# DIY_tool_-_Arduino_nano_shield_v1.net
KiCad netlist of a schematic drawn in EAGLE
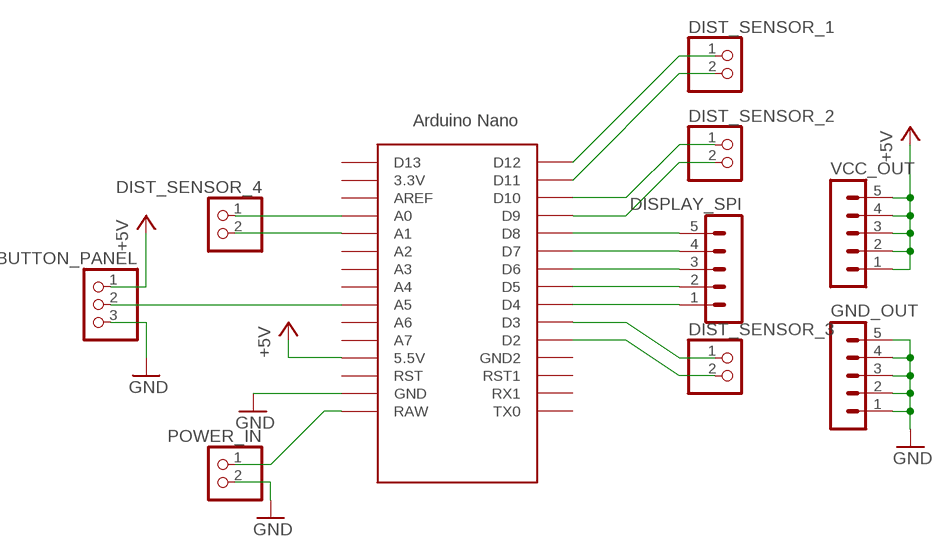
[diagram p0: schematic, sheet 1]

(export (version "E")
  (design (tool "Eeschema 10.0.6"))
  (components
    (comp (ref "BUTTON_PANEL")
      (value "PINHD-1X3")
      (footprint "eagle-import:1X03")
      (libsource (lib "eagle-import") (part "PINHD-1X3"))
    )
    (comp (ref "DISPLAY_SPI")
      (value "MA05-1")
      (footprint "eagle-import:MA05-1")
      (libsource (lib "eagle-import") (part "MA05-1"))
    )
    (comp (ref "DIST_SENSOR_1")
      (value "PINHD-1X2")
      (footprint "eagle-import:1X02")
      (libsource (lib "eagle-import") (part "PINHD-1X2"))
    )
    (comp (ref "DIST_SENSOR_2")
      (value "PINHD-1X2")
      (footprint "eagle-import:1X02")
      (libsource (lib "eagle-import") (part "PINHD-1X2"))
    )
    (comp (ref "DIST_SENSOR_3")
      (value "PINHD-1X2")
      (footprint "eagle-import:1X02")
      (libsource (lib "eagle-import") (part "PINHD-1X2"))
    )
    (comp (ref "DIST_SENSOR_4")
      (value "PINHD-1X2")
      (footprint "eagle-import:1X02")
      (libsource (lib "eagle-import") (part "PINHD-1X2"))
    )
    (comp (ref "GND_OUT")
      (value "MA05-1")
      (footprint "eagle-import:MA05-1")
      (libsource (lib "eagle-import") (part "MA05-1"))
    )
    (comp (ref "POWER_IN")
      (value "PINHD-1X2")
      (footprint "eagle-import:1X02")
      (libsource (lib "eagle-import") (part "PINHD-1X2"))
    )
    (comp (ref "U$1")
      (value "NANO")
      (footprint "eagle-import:NANO")
      (libsource (lib "eagle-import") (part "NANO"))
    )
    (comp (ref "VCC_OUT")
      (value "MA05-1")
      (footprint "eagle-import:MA05-1")
      (libsource (lib "eagle-import") (part "MA05-1"))
    )
  )
  (nets
    (net (code "1") (name "+5V") (class "Default")
      (node (ref "BUTTON_PANEL") (pin "1") (pinfunction "1_1") (pintype "passive"))
      (node (ref "U$1") (pin "5V") (pinfunction "5.5V_5V") (pintype "bidirectional"))
      (node (ref "VCC_OUT") (pin "1") (pinfunction "1_1") (pintype "passive"))
      (node (ref "VCC_OUT") (pin "2") (pinfunction "2_2") (pintype "passive"))
      (node (ref "VCC_OUT") (pin "3") (pinfunction "3_3") (pintype "passive"))
      (node (ref "VCC_OUT") (pin "4") (pinfunction "4_4") (pintype "passive"))
      (node (ref "VCC_OUT") (pin "5") (pinfunction "5_5") (pintype "passive"))
    )
    (net (code "2") (name "GND") (class "Default")
      (node (ref "BUTTON_PANEL") (pin "3") (pinfunction "3_3") (pintype "passive"))
      (node (ref "GND_OUT") (pin "1") (pinfunction "1_1") (pintype "passive"))
      (node (ref "GND_OUT") (pin "2") (pinfunction "2_2") (pintype "passive"))
      (node (ref "GND_OUT") (pin "3") (pinfunction "3_3") (pintype "passive"))
      (node (ref "GND_OUT") (pin "4") (pinfunction "4_4") (pintype "passive"))
      (node (ref "GND_OUT") (pin "5") (pinfunction "5_5") (pintype "passive"))
      (node (ref "POWER_IN") (pin "2") (pinfunction "2_2") (pintype "passive"))
      (node (ref "U$1") (pin "GND") (pinfunction "GND_GND") (pintype "bidirectional"))
    )
    (net (code "3") (name "Net-(BUTTON_PANEL-Pad2)") (class "Default")
      (node (ref "BUTTON_PANEL") (pin "2") (pinfunction "2_2") (pintype "passive"))
      (node (ref "U$1") (pin "A5") (pinfunction "A5_A5") (pintype "bidirectional"))
    )
    (net (code "4") (name "Net-(DISPLAY_SPI-Pad1)") (class "Default")
      (node (ref "DISPLAY_SPI") (pin "1") (pinfunction "1_1") (pintype "passive"))
      (node (ref "U$1") (pin "D4") (pinfunction "D4_D4") (pintype "bidirectional"))
    )
    (net (code "5") (name "Net-(DISPLAY_SPI-Pad2)") (class "Default")
      (node (ref "DISPLAY_SPI") (pin "2") (pinfunction "2_2") (pintype "passive"))
      (node (ref "U$1") (pin "D5") (pinfunction "D5_D5") (pintype "bidirectional"))
    )
    (net (code "6") (name "Net-(DISPLAY_SPI-Pad3)") (class "Default")
      (node (ref "DISPLAY_SPI") (pin "3") (pinfunction "3_3") (pintype "passive"))
      (node (ref "U$1") (pin "D6") (pinfunction "D6_D6") (pintype "bidirectional"))
    )
    (net (code "7") (name "Net-(DISPLAY_SPI-Pad4)") (class "Default")
      (node (ref "DISPLAY_SPI") (pin "4") (pinfunction "4_4") (pintype "passive"))
      (node (ref "U$1") (pin "D7") (pinfunction "D7_D7") (pintype "bidirectional"))
    )
    (net (code "8") (name "Net-(DISPLAY_SPI-Pad5)") (class "Default")
      (node (ref "DISPLAY_SPI") (pin "5") (pinfunction "5_5") (pintype "passive"))
      (node (ref "U$1") (pin "D8") (pinfunction "D8_D8") (pintype "bidirectional"))
    )
    (net (code "9") (name "Net-(DIST_SENSOR_1-Pad1)") (class "Default")
      (node (ref "DIST_SENSOR_1") (pin "1") (pinfunction "1_1") (pintype "passive"))
      (node (ref "U$1") (pin "D12") (pinfunction "D12_D12") (pintype "bidirectional"))
    )
    (net (code "10") (name "Net-(DIST_SENSOR_1-Pad2)") (class "Default")
      (node (ref "DIST_SENSOR_1") (pin "2") (pinfunction "2_2") (pintype "passive"))
      (node (ref "U$1") (pin "D11") (pinfunction "D11_D11") (pintype "bidirectional"))
    )
    (net (code "11") (name "Net-(DIST_SENSOR_2-Pad1)") (class "Default")
      (node (ref "DIST_SENSOR_2") (pin "1") (pinfunction "1_1") (pintype "passive"))
      (node (ref "U$1") (pin "D10") (pinfunction "D10_D10") (pintype "bidirectional"))
    )
    (net (code "12") (name "Net-(DIST_SENSOR_2-Pad2)") (class "Default")
      (node (ref "DIST_SENSOR_2") (pin "2") (pinfunction "2_2") (pintype "passive"))
      (node (ref "U$1") (pin "D9") (pinfunction "D9_D9") (pintype "bidirectional"))
    )
    (net (code "13") (name "Net-(DIST_SENSOR_3-Pad1)") (class "Default")
      (node (ref "DIST_SENSOR_3") (pin "1") (pinfunction "1_1") (pintype "passive"))
      (node (ref "U$1") (pin "D3") (pinfunction "D3_D3") (pintype "bidirectional"))
    )
    (net (code "14") (name "Net-(DIST_SENSOR_3-Pad2)") (class "Default")
      (node (ref "DIST_SENSOR_3") (pin "2") (pinfunction "2_2") (pintype "passive"))
      (node (ref "U$1") (pin "D2") (pinfunction "D2_D2") (pintype "bidirectional"))
    )
    (net (code "15") (name "Net-(DIST_SENSOR_4-Pad1)") (class "Default")
      (node (ref "DIST_SENSOR_4") (pin "1") (pinfunction "1_1") (pintype "passive"))
      (node (ref "U$1") (pin "A0") (pinfunction "A0_A0") (pintype "bidirectional"))
    )
    (net (code "16") (name "Net-(DIST_SENSOR_4-Pad2)") (class "Default")
      (node (ref "DIST_SENSOR_4") (pin "2") (pinfunction "2_2") (pintype "passive"))
      (node (ref "U$1") (pin "A1") (pinfunction "A1_A1") (pintype "bidirectional"))
    )
    (net (code "17") (name "Net-(POWER_IN-Pad1)") (class "Default")
      (node (ref "POWER_IN") (pin "1") (pinfunction "1_1") (pintype "passive"))
      (node (ref "U$1") (pin "RAW") (pinfunction "RAW_RAW") (pintype "bidirectional"))
    )
    (net (code "18") (name "unconnected-(U$1-GND2-PadGND1)") (class "Default")
      (node (ref "U$1") (pin "GND1") (pinfunction "GND2_GND1") (pintype "bidirectional"))
    )
    (net (code "19") (name "unconnected-(U$1-Pad3.3V)") (class "Default")
      (node (ref "U$1") (pin "3.3V") (pinfunction "3.3V_3.3V") (pintype "bidirectional"))
    )
    (net (code "20") (name "unconnected-(U$1-PadA2)") (class "Default")
      (node (ref "U$1") (pin "A2") (pinfunction "A2_A2") (pintype "bidirectional"))
    )
    (net (code "21") (name "unconnected-(U$1-PadA3)") (class "Default")
      (node (ref "U$1") (pin "A3") (pinfunction "A3_A3") (pintype "bidirectional"))
    )
    (net (code "22") (name "unconnected-(U$1-PadA4)") (class "Default")
      (node (ref "U$1") (pin "A4") (pinfunction "A4_A4") (pintype "bidirectional"))
    )
    (net (code "23") (name "unconnected-(U$1-PadA6)") (class "Default")
      (node (ref "U$1") (pin "A6") (pinfunction "A6_A6") (pintype "bidirectional"))
    )
    (net (code "24") (name "unconnected-(U$1-PadA7)") (class "Default")
      (node (ref "U$1") (pin "A7") (pinfunction "A7_A7") (pintype "bidirectional"))
    )
    (net (code "25") (name "unconnected-(U$1-PadAREF)") (class "Default")
      (node (ref "U$1") (pin "AREF") (pinfunction "AREF_AREF") (pintype "bidirectional"))
    )
    (net (code "26") (name "unconnected-(U$1-PadD13)") (class "Default")
      (node (ref "U$1") (pin "D13") (pinfunction "D13_D13") (pintype "bidirectional"))
    )
    (net (code "27") (name "unconnected-(U$1-PadICSP1)") (class "Default")
      (node (ref "U$1") (pin "ICSP1") (pinfunction "ICSP1_ICSP1") (pintype "bidirectional"))
    )
    (net (code "28") (name "unconnected-(U$1-PadICSP2)") (class "Default")
      (node (ref "U$1") (pin "ICSP2") (pinfunction "ICSP2_ICSP2") (pintype "bidirectional"))
    )
    (net (code "29") (name "unconnected-(U$1-PadICSP3)") (class "Default")
      (node (ref "U$1") (pin "ICSP3") (pinfunction "ICSP3_ICSP3") (pintype "bidirectional"))
    )
    (net (code "30") (name "unconnected-(U$1-PadICSP4)") (class "Default")
      (node (ref "U$1") (pin "ICSP4") (pinfunction "ICSP4_ICSP4") (pintype "bidirectional"))
    )
    (net (code "31") (name "unconnected-(U$1-PadICSP5)") (class "Default")
      (node (ref "U$1") (pin "ICSP5") (pinfunction "ICSP5_ICSP5") (pintype "bidirectional"))
    )
    (net (code "32") (name "unconnected-(U$1-PadICSP6)") (class "Default")
      (node (ref "U$1") (pin "ICSP6") (pinfunction "ICSP6_ICSP6") (pintype "bidirectional"))
    )
    (net (code "33") (name "unconnected-(U$1-PadRST)") (class "Default")
      (node (ref "U$1") (pin "RST") (pinfunction "RST_RST") (pintype "bidirectional"))
    )
    (net (code "34") (name "unconnected-(U$1-PadRST1)") (class "Default")
      (node (ref "U$1") (pin "RST1") (pinfunction "RST1_RST1") (pintype "bidirectional"))
    )
    (net (code "35") (name "unconnected-(U$1-PadRX1)") (class "Default")
      (node (ref "U$1") (pin "RX1") (pinfunction "RX1_RX1") (pintype "bidirectional"))
    )
    (net (code "36") (name "unconnected-(U$1-PadTX0)") (class "Default")
      (node (ref "U$1") (pin "TX0") (pinfunction "TX0_TX0") (pintype "bidirectional"))
    )
  )
)
